# SMARC_Pinout-2.net
KiCad netlist of a schematic drawn in Altium Designer
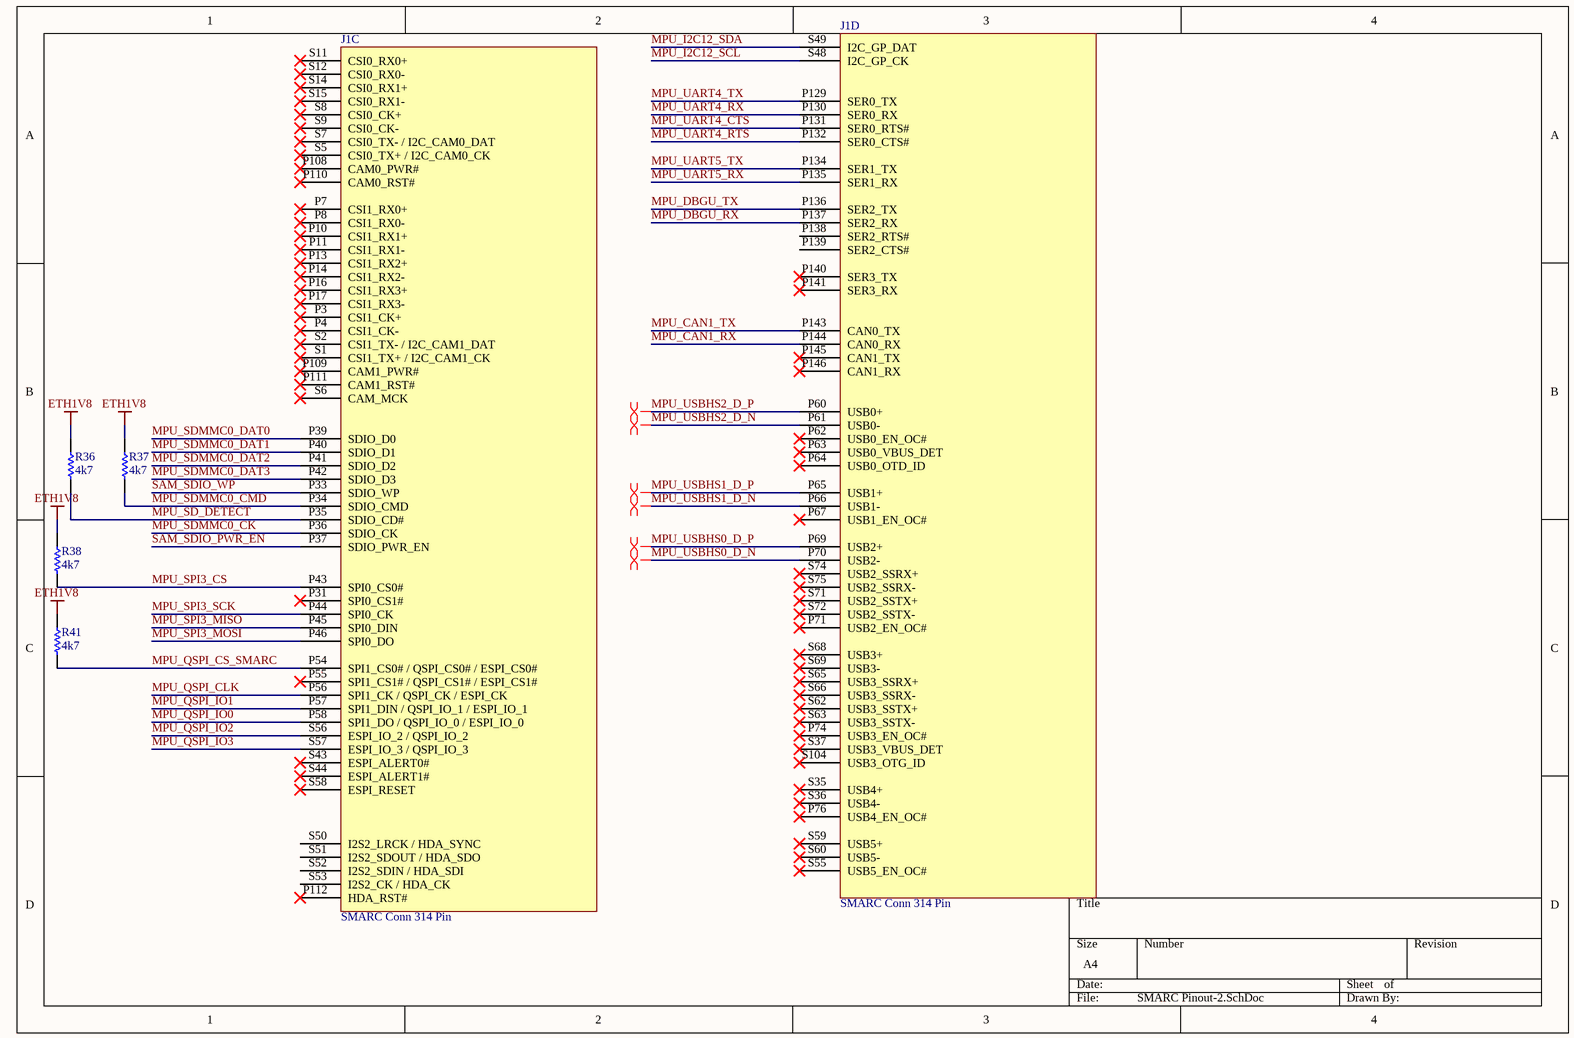
[diagram p0: SMARC Pinout-2.SchDoc]

(export (version "E")
  (design (tool "Eeschema 10.0.6"))
  (components
    (comp (ref "J1")
      (value "SMARC Conn 314 Pin")
      (footprint "SMARC Conn 314 Pin")
      (libsource (lib "Master") (part "SMARC Conn 314 Pin"))
    )
    (comp (ref "R36")
      (value "4k7")
      (footprint "RES-0201")
      (description "Resistor chip. 0201")
      (libsource (lib "Master") (part "RES-0201"))
    )
    (comp (ref "R37")
      (value "4k7")
      (footprint "RES-0201")
      (description "Resistor chip. 0201")
      (libsource (lib "Master") (part "RES-0201"))
    )
    (comp (ref "R38")
      (value "4k7")
      (footprint "RES-0201")
      (description "Resistor chip. 0201")
      (libsource (lib "Master") (part "RES-0201"))
    )
    (comp (ref "R41")
      (value "4k7")
      (footprint "RES-0201")
      (description "Resistor chip. 0201")
      (libsource (lib "Master") (part "RES-0201"))
    )
  )
  (nets
    (net (code "1") (name "/MPU_CAN1_RX") (class "Default")
      (node (ref "J1") (pin "P144") (pinfunction "CAN0_RX_P144") (pintype "passive"))
    )
    (net (code "2") (name "/MPU_CAN1_TX") (class "Default")
      (node (ref "J1") (pin "P143") (pinfunction "CAN0_TX_P143") (pintype "passive"))
    )
    (net (code "3") (name "/MPU_DBGU_RX") (class "Default")
      (node (ref "J1") (pin "P137") (pinfunction "SER2_RX_P137") (pintype "passive"))
    )
    (net (code "4") (name "/MPU_DBGU_TX") (class "Default")
      (node (ref "J1") (pin "P136") (pinfunction "SER2_TX_P136") (pintype "passive"))
    )
    (net (code "5") (name "/MPU_I2C12_SCL") (class "Default")
      (node (ref "J1") (pin "S48") (pinfunction "I2C_GP_CK_S48") (pintype "passive"))
    )
    (net (code "6") (name "/MPU_I2C12_SDA") (class "Default")
      (node (ref "J1") (pin "S49") (pinfunction "I2C_GP_DAT_S49") (pintype "passive"))
    )
    (net (code "7") (name "/MPU_QSPI_CLK") (class "Default")
      (node (ref "J1") (pin "P56") (pinfunction "SPI1_CK_/_QSPI_CK_/_ESPI_CK_P56") (pintype "passive"))
    )
    (net (code "8") (name "/MPU_QSPI_CS_SMARC") (class "Default")
      (node (ref "J1") (pin "P54") (pinfunction "SPI1_CS0#_/_QSPI_CS0#_/_ESPI_CS0#_P54") (pintype "passive"))
      (node (ref "R41") (pin "1") (pintype "passive"))
    )
    (net (code "9") (name "/MPU_QSPI_IO0") (class "Default")
      (node (ref "J1") (pin "P58") (pinfunction "SPI1_DO_/_QSPI_IO_0_/_ESPI_IO_0_P58") (pintype "passive"))
    )
    (net (code "10") (name "/MPU_QSPI_IO1") (class "Default")
      (node (ref "J1") (pin "P57") (pinfunction "SPI1_DIN_/_QSPI_IO_1_/_ESPI_IO_1_P57") (pintype "passive"))
    )
    (net (code "11") (name "/MPU_QSPI_IO2") (class "Default")
      (node (ref "J1") (pin "S56") (pinfunction "ESPI_IO_2_/_QSPI_IO_2_S56") (pintype "passive"))
    )
    (net (code "12") (name "/MPU_QSPI_IO3") (class "Default")
      (node (ref "J1") (pin "S57") (pinfunction "ESPI_IO_3_/_QSPI_IO_3_S57") (pintype "passive"))
    )
    (net (code "13") (name "/MPU_SDMMC0_CK") (class "Default")
      (node (ref "J1") (pin "P36") (pinfunction "SDIO_CK_P36") (pintype "passive"))
    )
    (net (code "14") (name "/MPU_SDMMC0_CMD") (class "Default")
      (node (ref "J1") (pin "P34") (pinfunction "SDIO_CMD_P34") (pintype "passive"))
      (node (ref "R37") (pin "1") (pintype "passive"))
    )
    (net (code "15") (name "/MPU_SDMMC0_DAT0") (class "Default")
      (node (ref "J1") (pin "P39") (pinfunction "SDIO_D0_P39") (pintype "passive"))
    )
    (net (code "16") (name "/MPU_SDMMC0_DAT1") (class "Default")
      (node (ref "J1") (pin "P40") (pinfunction "SDIO_D1_P40") (pintype "passive"))
    )
    (net (code "17") (name "/MPU_SDMMC0_DAT2") (class "Default")
      (node (ref "J1") (pin "P41") (pinfunction "SDIO_D2_P41") (pintype "passive"))
    )
    (net (code "18") (name "/MPU_SDMMC0_DAT3") (class "Default")
      (node (ref "J1") (pin "P42") (pinfunction "SDIO_D3_P42") (pintype "passive"))
    )
    (net (code "19") (name "/MPU_SD_DETECT") (class "Default")
      (node (ref "J1") (pin "P35") (pinfunction "SDIO_CD#_P35") (pintype "passive"))
      (node (ref "R36") (pin "1") (pintype "passive"))
    )
    (net (code "20") (name "/MPU_SPI3_CS") (class "Default")
      (node (ref "J1") (pin "P43") (pinfunction "SPI0_CS0#_P43") (pintype "passive"))
      (node (ref "R38") (pin "1") (pintype "passive"))
    )
    (net (code "21") (name "/MPU_SPI3_MISO") (class "Default")
      (node (ref "J1") (pin "P45") (pinfunction "SPI0_DIN_P45") (pintype "passive"))
    )
    (net (code "22") (name "/MPU_SPI3_MOSI") (class "Default")
      (node (ref "J1") (pin "P46") (pinfunction "SPI0_DO_P46") (pintype "passive"))
    )
    (net (code "23") (name "/MPU_SPI3_SCK") (class "Default")
      (node (ref "J1") (pin "P44") (pinfunction "SPI0_CK_P44") (pintype "passive"))
    )
    (net (code "24") (name "/MPU_UART4_CTS") (class "Default")
      (node (ref "J1") (pin "P131") (pinfunction "SER0_RTS#_P131") (pintype "passive"))
    )
    (net (code "25") (name "/MPU_UART4_RTS") (class "Default")
      (node (ref "J1") (pin "P132") (pinfunction "SER0_CTS#_P132") (pintype "passive"))
    )
    (net (code "26") (name "/MPU_UART4_RX") (class "Default")
      (node (ref "J1") (pin "P130") (pinfunction "SER0_RX_P130") (pintype "passive"))
    )
    (net (code "27") (name "/MPU_UART4_TX") (class "Default")
      (node (ref "J1") (pin "P129") (pinfunction "SER0_TX_P129") (pintype "passive"))
    )
    (net (code "28") (name "/MPU_UART5_RX") (class "Default")
      (node (ref "J1") (pin "P135") (pinfunction "SER1_RX_P135") (pintype "passive"))
    )
    (net (code "29") (name "/MPU_UART5_TX") (class "Default")
      (node (ref "J1") (pin "P134") (pinfunction "SER1_TX_P134") (pintype "passive"))
    )
    (net (code "30") (name "/MPU_USBHS0_D_N") (class "Default")
      (node (ref "J1") (pin "P70") (pinfunction "USB2-_P70") (pintype "passive"))
    )
    (net (code "31") (name "/MPU_USBHS0_D_P") (class "Default")
      (node (ref "J1") (pin "P69") (pinfunction "USB2+_P69") (pintype "passive"))
    )
    (net (code "32") (name "/MPU_USBHS1_D_N") (class "Default")
      (node (ref "J1") (pin "P66") (pinfunction "USB1-_P66") (pintype "passive"))
    )
    (net (code "33") (name "/MPU_USBHS1_D_P") (class "Default")
      (node (ref "J1") (pin "P65") (pinfunction "USB1+_P65") (pintype "passive"))
    )
    (net (code "34") (name "/MPU_USBHS2_D_N") (class "Default")
      (node (ref "J1") (pin "P61") (pinfunction "USB0-_P61") (pintype "passive"))
    )
    (net (code "35") (name "/MPU_USBHS2_D_P") (class "Default")
      (node (ref "J1") (pin "P60") (pinfunction "USB0+_P60") (pintype "passive"))
    )
    (net (code "36") (name "/SAM_SDIO_PWR_EN") (class "Default")
      (node (ref "J1") (pin "P37") (pinfunction "SDIO_PWR_EN_P37") (pintype "passive"))
    )
    (net (code "37") (name "/SAM_SDIO_WP") (class "Default")
      (node (ref "J1") (pin "P33") (pinfunction "SDIO_WP_P33") (pintype "passive"))
    )
    (net (code "38") (name "ETH1V8") (class "Default")
      (node (ref "R36") (pin "2") (pintype "passive"))
      (node (ref "R37") (pin "2") (pintype "passive"))
      (node (ref "R38") (pin "2") (pintype "passive"))
      (node (ref "R41") (pin "2") (pintype "passive"))
    )
    (net (code "39") (name "unconnected-(J1C-CAM0_PWR#-PadP108)") (class "Default")
      (node (ref "J1") (pin "P108") (pinfunction "CAM0_PWR#_P108") (pintype "passive+no_connect"))
    )
    (net (code "40") (name "unconnected-(J1C-CAM0_RST#-PadP110)") (class "Default")
      (node (ref "J1") (pin "P110") (pinfunction "CAM0_RST#_P110") (pintype "passive+no_connect"))
    )
    (net (code "41") (name "unconnected-(J1C-CAM1_PWR#-PadP109)") (class "Default")
      (node (ref "J1") (pin "P109") (pinfunction "CAM1_PWR#_P109") (pintype "passive+no_connect"))
    )
    (net (code "42") (name "unconnected-(J1C-CAM1_RST#-PadP111)") (class "Default")
      (node (ref "J1") (pin "P111") (pinfunction "CAM1_RST#_P111") (pintype "passive+no_connect"))
    )
    (net (code "43") (name "unconnected-(J1C-CAM_MCK-PadS6)") (class "Default")
      (node (ref "J1") (pin "S6") (pinfunction "CAM_MCK_S6") (pintype "passive+no_connect"))
    )
    (net (code "44") (name "unconnected-(J1C-CSI0_CK+-PadS8)") (class "Default")
      (node (ref "J1") (pin "S8") (pinfunction "CSI0_CK+_S8") (pintype "passive+no_connect"))
    )
    (net (code "45") (name "unconnected-(J1C-CSI0_CK--PadS9)") (class "Default")
      (node (ref "J1") (pin "S9") (pinfunction "CSI0_CK-_S9") (pintype "passive+no_connect"))
    )
    (net (code "46") (name "unconnected-(J1C-CSI0_RX0+-PadS11)") (class "Default")
      (node (ref "J1") (pin "S11") (pinfunction "CSI0_RX0+_S11") (pintype "passive+no_connect"))
    )
    (net (code "47") (name "unconnected-(J1C-CSI0_RX0--PadS12)") (class "Default")
      (node (ref "J1") (pin "S12") (pinfunction "CSI0_RX0-_S12") (pintype "passive+no_connect"))
    )
    (net (code "48") (name "unconnected-(J1C-CSI0_RX1+-PadS14)") (class "Default")
      (node (ref "J1") (pin "S14") (pinfunction "CSI0_RX1+_S14") (pintype "passive+no_connect"))
    )
    (net (code "49") (name "unconnected-(J1C-CSI0_RX1--PadS15)") (class "Default")
      (node (ref "J1") (pin "S15") (pinfunction "CSI0_RX1-_S15") (pintype "passive+no_connect"))
    )
    (net (code "50") (name "unconnected-(J1C-CSI0_TX+_{slash}_I2C_CAM0_CK-PadS5)") (class "Default")
      (node (ref "J1") (pin "S5") (pinfunction "CSI0_TX+_/_I2C_CAM0_CK_S5") (pintype "passive+no_connect"))
    )
    (net (code "51") (name "unconnected-(J1C-CSI0_TX-_{slash}_I2C_CAM0_DAT-PadS7)") (class "Default")
      (node (ref "J1") (pin "S7") (pinfunction "CSI0_TX-_/_I2C_CAM0_DAT_S7") (pintype "passive+no_connect"))
    )
    (net (code "52") (name "unconnected-(J1C-CSI1_CK+-PadP3)") (class "Default")
      (node (ref "J1") (pin "P3") (pinfunction "CSI1_CK+_P3") (pintype "passive+no_connect"))
    )
    (net (code "53") (name "unconnected-(J1C-CSI1_CK--PadP4)") (class "Default")
      (node (ref "J1") (pin "P4") (pinfunction "CSI1_CK-_P4") (pintype "passive+no_connect"))
    )
    (net (code "54") (name "unconnected-(J1C-CSI1_RX0+-PadP7)") (class "Default")
      (node (ref "J1") (pin "P7") (pinfunction "CSI1_RX0+_P7") (pintype "passive+no_connect"))
    )
    (net (code "55") (name "unconnected-(J1C-CSI1_RX0--PadP8)") (class "Default")
      (node (ref "J1") (pin "P8") (pinfunction "CSI1_RX0-_P8") (pintype "passive+no_connect"))
    )
    (net (code "56") (name "unconnected-(J1C-CSI1_RX1+-PadP10)") (class "Default")
      (node (ref "J1") (pin "P10") (pinfunction "CSI1_RX1+_P10") (pintype "passive+no_connect"))
    )
    (net (code "57") (name "unconnected-(J1C-CSI1_RX1--PadP11)") (class "Default")
      (node (ref "J1") (pin "P11") (pinfunction "CSI1_RX1-_P11") (pintype "passive+no_connect"))
    )
    (net (code "58") (name "unconnected-(J1C-CSI1_RX2+-PadP13)") (class "Default")
      (node (ref "J1") (pin "P13") (pinfunction "CSI1_RX2+_P13") (pintype "passive+no_connect"))
    )
    (net (code "59") (name "unconnected-(J1C-CSI1_RX2--PadP14)") (class "Default")
      (node (ref "J1") (pin "P14") (pinfunction "CSI1_RX2-_P14") (pintype "passive+no_connect"))
    )
    (net (code "60") (name "unconnected-(J1C-CSI1_RX3+-PadP16)") (class "Default")
      (node (ref "J1") (pin "P16") (pinfunction "CSI1_RX3+_P16") (pintype "passive+no_connect"))
    )
    (net (code "61") (name "unconnected-(J1C-CSI1_RX3--PadP17)") (class "Default")
      (node (ref "J1") (pin "P17") (pinfunction "CSI1_RX3-_P17") (pintype "passive+no_connect"))
    )
    (net (code "62") (name "unconnected-(J1C-CSI1_TX+_{slash}_I2C_CAM1_CK-PadS1)") (class "Default")
      (node (ref "J1") (pin "S1") (pinfunction "CSI1_TX+_/_I2C_CAM1_CK_S1") (pintype "passive+no_connect"))
    )
    (net (code "63") (name "unconnected-(J1C-CSI1_TX-_{slash}_I2C_CAM1_DAT-PadS2)") (class "Default")
      (node (ref "J1") (pin "S2") (pinfunction "CSI1_TX-_/_I2C_CAM1_DAT_S2") (pintype "passive+no_connect"))
    )
    (net (code "64") (name "unconnected-(J1C-ESPI_ALERT0#-PadS43)") (class "Default")
      (node (ref "J1") (pin "S43") (pinfunction "ESPI_ALERT0#_S43") (pintype "passive+no_connect"))
    )
    (net (code "65") (name "unconnected-(J1C-ESPI_ALERT1#-PadS44)") (class "Default")
      (node (ref "J1") (pin "S44") (pinfunction "ESPI_ALERT1#_S44") (pintype "passive+no_connect"))
    )
    (net (code "66") (name "unconnected-(J1C-ESPI_RESET-PadS58)") (class "Default")
      (node (ref "J1") (pin "S58") (pinfunction "ESPI_RESET_S58") (pintype "passive+no_connect"))
    )
    (net (code "67") (name "unconnected-(J1C-HDA_RST#-PadP112)") (class "Default")
      (node (ref "J1") (pin "P112") (pinfunction "HDA_RST#_P112") (pintype "passive+no_connect"))
    )
    (net (code "68") (name "unconnected-(J1C-I2S2_CK_{slash}_HDA_CK-PadS53)") (class "Default")
      (node (ref "J1") (pin "S53") (pinfunction "I2S2_CK_/_HDA_CK_S53") (pintype "passive"))
    )
    (net (code "69") (name "unconnected-(J1C-I2S2_LRCK_{slash}_HDA_SYNC-PadS50)") (class "Default")
      (node (ref "J1") (pin "S50") (pinfunction "I2S2_LRCK_/_HDA_SYNC_S50") (pintype "passive"))
    )
    (net (code "70") (name "unconnected-(J1C-I2S2_SDIN_{slash}_HDA_SDI-PadS52)") (class "Default")
      (node (ref "J1") (pin "S52") (pinfunction "I2S2_SDIN_/_HDA_SDI_S52") (pintype "passive"))
    )
    (net (code "71") (name "unconnected-(J1C-I2S2_SDOUT_{slash}_HDA_SDO-PadS51)") (class "Default")
      (node (ref "J1") (pin "S51") (pinfunction "I2S2_SDOUT_/_HDA_SDO_S51") (pintype "passive"))
    )
    (net (code "72") (name "unconnected-(J1C-SPI0_CS1#-PadP31)") (class "Default")
      (node (ref "J1") (pin "P31") (pinfunction "SPI0_CS1#_P31") (pintype "passive+no_connect"))
    )
    (net (code "73") (name "unconnected-(J1C-SPI1_CS1#_{slash}_QSPI_CS1#_{slash}_ESPI_CS1#-PadP55)") (class "Default")
      (node (ref "J1") (pin "P55") (pinfunction "SPI1_CS1#_/_QSPI_CS1#_/_ESPI_CS1#_P55") (pintype "passive+no_connect"))
    )
    (net (code "74") (name "unconnected-(J1D-CAN1_RX-PadP146)") (class "Default")
      (node (ref "J1") (pin "P146") (pinfunction "CAN1_RX_P146") (pintype "passive+no_connect"))
    )
    (net (code "75") (name "unconnected-(J1D-CAN1_TX-PadP145)") (class "Default")
      (node (ref "J1") (pin "P145") (pinfunction "CAN1_TX_P145") (pintype "passive+no_connect"))
    )
    (net (code "76") (name "unconnected-(J1D-SER2_CTS#-PadP139)") (class "Default")
      (node (ref "J1") (pin "P139") (pinfunction "SER2_CTS#_P139") (pintype "passive"))
    )
    (net (code "77") (name "unconnected-(J1D-SER2_RTS#-PadP138)") (class "Default")
      (node (ref "J1") (pin "P138") (pinfunction "SER2_RTS#_P138") (pintype "passive"))
    )
    (net (code "78") (name "unconnected-(J1D-SER3_RX-PadP141)") (class "Default")
      (node (ref "J1") (pin "P141") (pinfunction "SER3_RX_P141") (pintype "passive+no_connect"))
    )
    (net (code "79") (name "unconnected-(J1D-SER3_TX-PadP140)") (class "Default")
      (node (ref "J1") (pin "P140") (pinfunction "SER3_TX_P140") (pintype "passive+no_connect"))
    )
    (net (code "80") (name "unconnected-(J1D-USB0_EN_OC#-PadP62)") (class "Default")
      (node (ref "J1") (pin "P62") (pinfunction "USB0_EN_OC#_P62") (pintype "passive+no_connect"))
    )
    (net (code "81") (name "unconnected-(J1D-USB0_OTD_ID-PadP64)") (class "Default")
      (node (ref "J1") (pin "P64") (pinfunction "USB0_OTD_ID_P64") (pintype "passive+no_connect"))
    )
    (net (code "82") (name "unconnected-(J1D-USB0_VBUS_DET-PadP63)") (class "Default")
      (node (ref "J1") (pin "P63") (pinfunction "USB0_VBUS_DET_P63") (pintype "passive+no_connect"))
    )
    (net (code "83") (name "unconnected-(J1D-USB1_EN_OC#-PadP67)") (class "Default")
      (node (ref "J1") (pin "P67") (pinfunction "USB1_EN_OC#_P67") (pintype "passive+no_connect"))
    )
    (net (code "84") (name "unconnected-(J1D-USB2_EN_OC#-PadP71)") (class "Default")
      (node (ref "J1") (pin "P71") (pinfunction "USB2_EN_OC#_P71") (pintype "passive+no_connect"))
    )
    (net (code "85") (name "unconnected-(J1D-USB2_SSRX+-PadS74)") (class "Default")
      (node (ref "J1") (pin "S74") (pinfunction "USB2_SSRX+_S74") (pintype "passive+no_connect"))
    )
    (net (code "86") (name "unconnected-(J1D-USB2_SSRX--PadS75)") (class "Default")
      (node (ref "J1") (pin "S75") (pinfunction "USB2_SSRX-_S75") (pintype "passive+no_connect"))
    )
    (net (code "87") (name "unconnected-(J1D-USB2_SSTX+-PadS71)") (class "Default")
      (node (ref "J1") (pin "S71") (pinfunction "USB2_SSTX+_S71") (pintype "passive+no_connect"))
    )
    (net (code "88") (name "unconnected-(J1D-USB2_SSTX--PadS72)") (class "Default")
      (node (ref "J1") (pin "S72") (pinfunction "USB2_SSTX-_S72") (pintype "passive+no_connect"))
    )
    (net (code "89") (name "unconnected-(J1D-USB3+-PadS68)") (class "Default")
      (node (ref "J1") (pin "S68") (pinfunction "USB3+_S68") (pintype "passive+no_connect"))
    )
    (net (code "90") (name "unconnected-(J1D-USB3--PadS69)") (class "Default")
      (node (ref "J1") (pin "S69") (pinfunction "USB3-_S69") (pintype "passive+no_connect"))
    )
    (net (code "91") (name "unconnected-(J1D-USB3_EN_OC#-PadP74)") (class "Default")
      (node (ref "J1") (pin "P74") (pinfunction "USB3_EN_OC#_P74") (pintype "passive+no_connect"))
    )
    (net (code "92") (name "unconnected-(J1D-USB3_OTG_ID-PadS104)") (class "Default")
      (node (ref "J1") (pin "S104") (pinfunction "USB3_OTG_ID_S104") (pintype "passive+no_connect"))
    )
    (net (code "93") (name "unconnected-(J1D-USB3_SSRX+-PadS65)") (class "Default")
      (node (ref "J1") (pin "S65") (pinfunction "USB3_SSRX+_S65") (pintype "passive+no_connect"))
    )
    (net (code "94") (name "unconnected-(J1D-USB3_SSRX--PadS66)") (class "Default")
      (node (ref "J1") (pin "S66") (pinfunction "USB3_SSRX-_S66") (pintype "passive+no_connect"))
    )
    (net (code "95") (name "unconnected-(J1D-USB3_SSTX+-PadS62)") (class "Default")
      (node (ref "J1") (pin "S62") (pinfunction "USB3_SSTX+_S62") (pintype "passive+no_connect"))
    )
    (net (code "96") (name "unconnected-(J1D-USB3_SSTX--PadS63)") (class "Default")
      (node (ref "J1") (pin "S63") (pinfunction "USB3_SSTX-_S63") (pintype "passive+no_connect"))
    )
    (net (code "97") (name "unconnected-(J1D-USB3_VBUS_DET-PadS37)") (class "Default")
      (node (ref "J1") (pin "S37") (pinfunction "USB3_VBUS_DET_S37") (pintype "passive+no_connect"))
    )
    (net (code "98") (name "unconnected-(J1D-USB4+-PadS35)") (class "Default")
      (node (ref "J1") (pin "S35") (pinfunction "USB4+_S35") (pintype "passive+no_connect"))
    )
    (net (code "99") (name "unconnected-(J1D-USB4--PadS36)") (class "Default")
      (node (ref "J1") (pin "S36") (pinfunction "USB4-_S36") (pintype "passive+no_connect"))
    )
    (net (code "100") (name "unconnected-(J1D-USB4_EN_OC#-PadP76)") (class "Default")
      (node (ref "J1") (pin "P76") (pinfunction "USB4_EN_OC#_P76") (pintype "passive+no_connect"))
    )
    (net (code "101") (name "unconnected-(J1D-USB5+-PadS59)") (class "Default")
      (node (ref "J1") (pin "S59") (pinfunction "USB5+_S59") (pintype "passive+no_connect"))
    )
    (net (code "102") (name "unconnected-(J1D-USB5--PadS60)") (class "Default")
      (node (ref "J1") (pin "S60") (pinfunction "USB5-_S60") (pintype "passive+no_connect"))
    )
    (net (code "103") (name "unconnected-(J1D-USB5_EN_OC#-PadS55)") (class "Default")
      (node (ref "J1") (pin "S55") (pinfunction "USB5_EN_OC#_S55") (pintype "passive+no_connect"))
    )
  )
)
